# Blutooth.net
KiCad netlist of a schematic drawn in Altium Designer
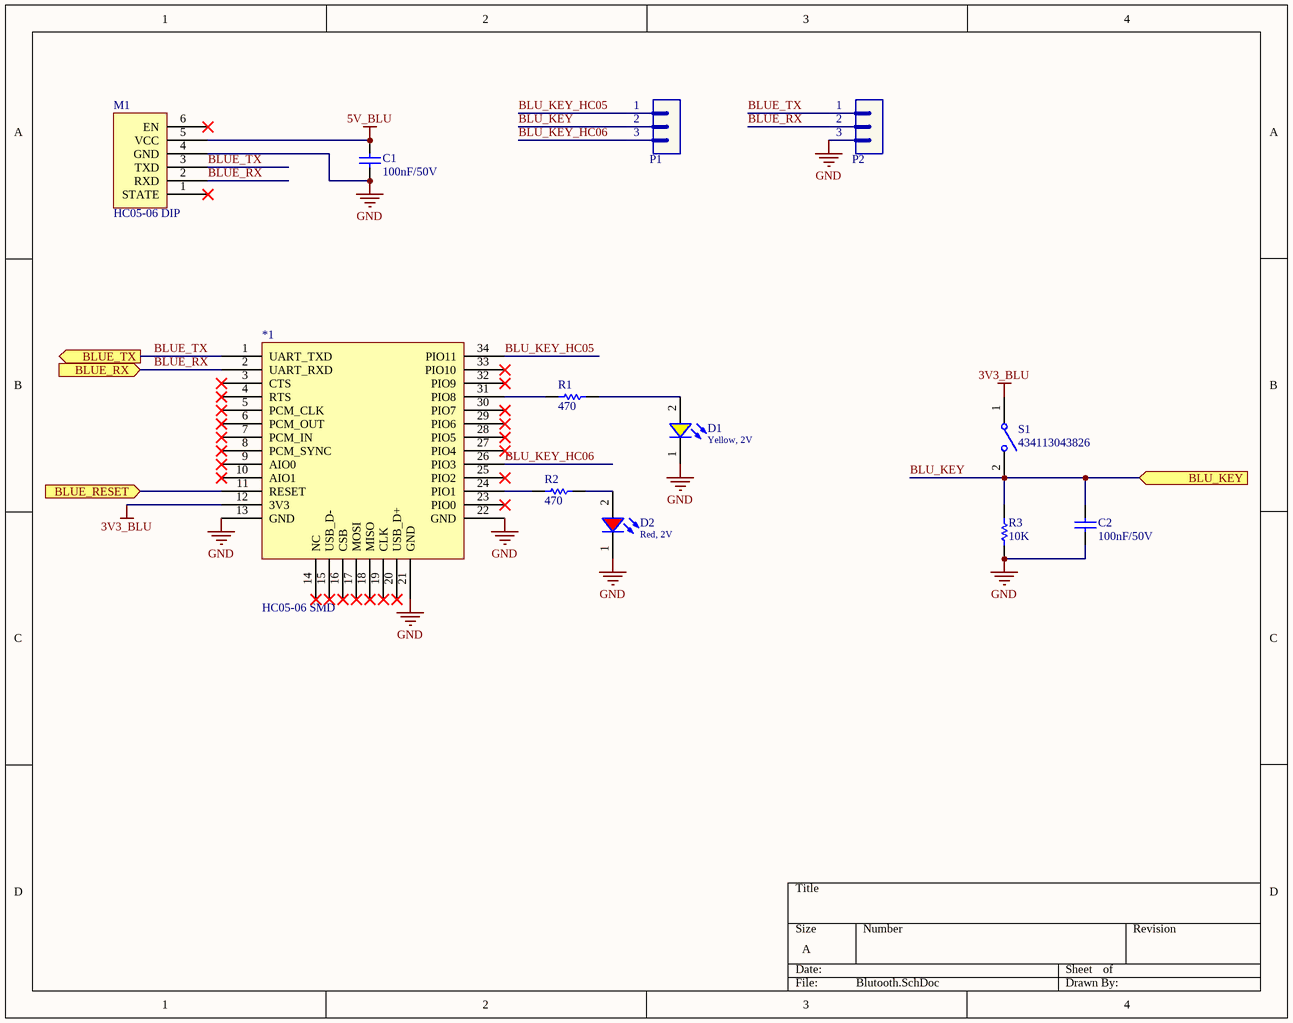
[diagram p0: Blutooth.SchDoc]

(export (version "E")
  (design (tool "Eeschema 10.0.6"))
  (components
    (comp (ref "*1")
      (value "HC05-06 SMD")
      (footprint "HC05-06 SMD")
      (libsource (lib "chicken") (part "HC05-06 SMD"))
    )
    (comp (ref "C1")
      (value "100nF/50V")
      (footprint "CAP-SM-0805")
      (description "CAP CER 0.1UF 50V Y5V 0805")
      (fields
        (field (name "MANUFACTURER") "Samsung Electro-Mechanics")
        (field (name "MANUFACTURER PART NUMBER") "CL21F104ZBCNNNC")
      )
      (libsource (lib "Capacitor") (part "Cap-100nF-50V-0805"))
    )
    (comp (ref "C2")
      (value "100nF/50V")
      (footprint "CAP-SM-0805")
      (description "CAP CER 0.1UF 50V Y5V 0805")
      (fields
        (field (name "MANUFACTURER") "Samsung Electro-Mechanics")
        (field (name "MANUFACTURER PART NUMBER") "CL21F104ZBCNNNC")
      )
      (libsource (lib "Capacitor") (part "Cap-100nF-50V-0805"))
    )
    (comp (ref "D1")
      (value "Yellow, 2V")
      (footprint "WL-SMCW_0805")
      (description "WL-SMCW SMT Mono-color Chip LED Waterclear, size 0805, Yellow, 2V, 140deg")
      (fields (field (name "PART NUMBER") "150080YS75000") (field (name "PUBLISHER") "Wurth Elektronik"))
      (libsource (lib "150080BS75000_Altium_WL-SMCW_rev20a") (part "150080YS75000"))
    )
    (comp (ref "D2")
      (value "Red, 2V")
      (footprint "WL-SMCW_0805")
      (description "WL-SMCW SMT Mono-color Chip LED Waterclear, size 0805, Red, 2V, 140deg")
      (fields (field (name "PART NUMBER") "150080RS75000") (field (name "PUBLISHER") "Wurth Elektronik"))
      (libsource (lib "150080BS75000_Altium_WL-SMCW_rev20a") (part "150080RS75000"))
    )
    (comp (ref "M1")
      (value "HC05-06 DIP")
      (footprint "HC05-06 DIP")
      (libsource (lib "chicken") (part "HC05-06 DIP"))
    )
    (comp (ref "P1")
      (value "Header 3")
      (footprint "JP3")
      (description "Header, 3-Pin")
      (fields (field (name "PUBLISHER") "Altium Limited"))
      (libsource (lib "Header-connector") (part "Header 3"))
    )
    (comp (ref "P2")
      (value "Header 3")
      (footprint "JP3")
      (description "Header, 3-Pin")
      (fields (field (name "PUBLISHER") "Altium Limited"))
      (libsource (lib "Header-connector") (part "Header 3"))
    )
    (comp (ref "R1")
      (value "470")
      (footprint "Resistor:RES-SM-0805")
      (description "RES 470 OHM JUMPER 0805")
      (fields
        (field (name "MANUFACTURER") "YAG6006CT-ND")
        (field (name "MANUFACTURER PART NUMBER") "PE0805FRF7W0R047L")
      )
      (libsource (lib "Resistor") (part "Res-470-0805"))
    )
    (comp (ref "R2")
      (value "470")
      (footprint "Resistor:RES-SM-0805")
      (description "RES 470 OHM JUMPER 0805")
      (fields
        (field (name "MANUFACTURER") "YAG6006CT-ND")
        (field (name "MANUFACTURER PART NUMBER") "PE0805FRF7W0R047L")
      )
      (libsource (lib "Resistor") (part "Res-470-0805"))
    )
    (comp (ref "R3")
      (value "10K")
      (footprint "Resistor:RES-SM-0805")
      (description "RES 10K OHM 1% 1/4W 0805")
      (fields
        (field (name "MANUFACTURER") "Stackpole Electronics Inc")
        (field (name "MANUFACTURER PART NUMBER") "RNCP0805FTD10K0")
      )
      (libsource (lib "Resistor") (part "Res-10k-0805"))
    )
    (comp (ref "S1")
      (value "434113043826")
      (footprint "434113043826")
      (description "WS-TASV J-Bend SMT Tact Switch 6x3.5mm, height 4.3mm, 260gf")
      (fields (field (name "PUBLISHER") "Wurth Elektronik"))
      (libsource (lib "434113043826_Altium_WS-TASV_rev20a") (part "434113043826"))
    )
  )
  (nets
    (net (code "1") (name "/BLUE_RESET") (class "Default")
      (node (ref "*1") (pin "11") (pinfunction "RESET_11") (pintype "passive"))
    )
    (net (code "2") (name "/BLUE_RX") (class "Default")
      (node (ref "*1") (pin "2") (pinfunction "UART_RXD_2") (pintype "passive"))
      (node (ref "M1") (pin "2") (pinfunction "RXD_2") (pintype "passive"))
      (node (ref "P2") (pin "2") (pinfunction "2_2") (pintype "passive"))
    )
    (net (code "3") (name "/BLUE_TX") (class "Default")
      (node (ref "*1") (pin "1") (pinfunction "UART_TXD_1") (pintype "passive"))
      (node (ref "M1") (pin "3") (pinfunction "TXD_3") (pintype "passive"))
      (node (ref "P2") (pin "1") (pinfunction "1_1") (pintype "passive"))
    )
    (net (code "4") (name "/BLU_KEY") (class "Default")
      (node (ref "C2") (pin "2") (pinfunction "2_2") (pintype "passive"))
      (node (ref "P1") (pin "2") (pinfunction "2_2") (pintype "passive"))
      (node (ref "R3") (pin "1") (pinfunction "1_1") (pintype "passive"))
      (node (ref "S1") (pin "2") (pinfunction "2_2") (pintype "passive"))
    )
    (net (code "5") (name "/BLU_KEY_HC05") (class "Default")
      (node (ref "*1") (pin "34") (pinfunction "PIO11_34") (pintype "passive"))
      (node (ref "P1") (pin "1") (pinfunction "1_1") (pintype "passive"))
    )
    (net (code "6") (name "/BLU_KEY_HC06") (class "Default")
      (node (ref "*1") (pin "26") (pinfunction "PIO3_26") (pintype "passive"))
      (node (ref "P1") (pin "3") (pinfunction "3_3") (pintype "passive"))
    )
    (net (code "7") (name "3V3_BLU") (class "Default")
      (node (ref "*1") (pin "12") (pinfunction "3V3_12") (pintype "passive"))
      (node (ref "S1") (pin "1") (pinfunction "1_1") (pintype "passive"))
    )
    (net (code "8") (name "5V_BLU") (class "Default")
      (node (ref "C1") (pin "2") (pinfunction "2_2") (pintype "passive"))
      (node (ref "M1") (pin "5") (pinfunction "VCC_5") (pintype "passive"))
    )
    (net (code "9") (name "GND") (class "Default")
      (node (ref "*1") (pin "13") (pinfunction "GND_13") (pintype "passive"))
      (node (ref "*1") (pin "21") (pinfunction "GND_21") (pintype "passive"))
      (node (ref "*1") (pin "22") (pinfunction "GND_22") (pintype "passive"))
      (node (ref "C1") (pin "1") (pinfunction "1_1") (pintype "passive"))
      (node (ref "C2") (pin "1") (pinfunction "1_1") (pintype "passive"))
      (node (ref "D1") (pin "1") (pinfunction "K_1") (pintype "passive"))
      (node (ref "D2") (pin "1") (pinfunction "K_1") (pintype "passive"))
      (node (ref "M1") (pin "4") (pinfunction "GND_4") (pintype "passive"))
      (node (ref "P2") (pin "3") (pinfunction "3_3") (pintype "passive"))
      (node (ref "R3") (pin "2") (pinfunction "2_2") (pintype "passive"))
    )
    (net (code "10") (name "Net-(*1-PIO1)") (class "Default")
      (node (ref "*1") (pin "24") (pinfunction "PIO1_24") (pintype "passive"))
      (node (ref "R2") (pin "1") (pinfunction "1_1") (pintype "passive"))
    )
    (net (code "11") (name "Net-(*1-PIO8)") (class "Default")
      (node (ref "*1") (pin "31") (pinfunction "PIO8_31") (pintype "passive"))
      (node (ref "R1") (pin "1") (pinfunction "1_1") (pintype "passive"))
    )
    (net (code "12") (name "Net-(D1-A)") (class "Default")
      (node (ref "D1") (pin "2") (pinfunction "A_2") (pintype "passive"))
      (node (ref "R1") (pin "2") (pinfunction "2_2") (pintype "passive"))
    )
    (net (code "13") (name "Net-(D2-A)") (class "Default")
      (node (ref "D2") (pin "2") (pinfunction "A_2") (pintype "passive"))
      (node (ref "R2") (pin "2") (pinfunction "2_2") (pintype "passive"))
    )
    (net (code "14") (name "unconnected-(*1-AIO0-Pad9)") (class "Default")
      (node (ref "*1") (pin "9") (pinfunction "AIO0_9") (pintype "passive+no_connect"))
    )
    (net (code "15") (name "unconnected-(*1-AIO1-Pad10)") (class "Default")
      (node (ref "*1") (pin "10") (pinfunction "AIO1_10") (pintype "passive+no_connect"))
    )
    (net (code "16") (name "unconnected-(*1-CLK-Pad19)") (class "Default")
      (node (ref "*1") (pin "19") (pinfunction "CLK_19") (pintype "passive+no_connect"))
    )
    (net (code "17") (name "unconnected-(*1-CSB-Pad16)") (class "Default")
      (node (ref "*1") (pin "16") (pinfunction "CSB_16") (pintype "passive+no_connect"))
    )
    (net (code "18") (name "unconnected-(*1-CTS-Pad3)") (class "Default")
      (node (ref "*1") (pin "3") (pinfunction "CTS_3") (pintype "passive+no_connect"))
    )
    (net (code "19") (name "unconnected-(*1-MISO-Pad18)") (class "Default")
      (node (ref "*1") (pin "18") (pinfunction "MISO_18") (pintype "passive+no_connect"))
    )
    (net (code "20") (name "unconnected-(*1-MOSI-Pad17)") (class "Default")
      (node (ref "*1") (pin "17") (pinfunction "MOSI_17") (pintype "passive+no_connect"))
    )
    (net (code "21") (name "unconnected-(*1-NC-Pad14)") (class "Default")
      (node (ref "*1") (pin "14") (pinfunction "NC_14") (pintype "passive+no_connect"))
    )
    (net (code "22") (name "unconnected-(*1-PCM_CLK-Pad5)") (class "Default")
      (node (ref "*1") (pin "5") (pinfunction "PCM_CLK_5") (pintype "passive+no_connect"))
    )
    (net (code "23") (name "unconnected-(*1-PCM_IN-Pad7)") (class "Default")
      (node (ref "*1") (pin "7") (pinfunction "PCM_IN_7") (pintype "passive+no_connect"))
    )
    (net (code "24") (name "unconnected-(*1-PCM_OUT-Pad6)") (class "Default")
      (node (ref "*1") (pin "6") (pinfunction "PCM_OUT_6") (pintype "passive+no_connect"))
    )
    (net (code "25") (name "unconnected-(*1-PCM_SYNC-Pad8)") (class "Default")
      (node (ref "*1") (pin "8") (pinfunction "PCM_SYNC_8") (pintype "passive+no_connect"))
    )
    (net (code "26") (name "unconnected-(*1-PIO0-Pad23)") (class "Default")
      (node (ref "*1") (pin "23") (pinfunction "PIO0_23") (pintype "passive+no_connect"))
    )
    (net (code "27") (name "unconnected-(*1-PIO2-Pad25)") (class "Default")
      (node (ref "*1") (pin "25") (pinfunction "PIO2_25") (pintype "passive+no_connect"))
    )
    (net (code "28") (name "unconnected-(*1-PIO4-Pad27)") (class "Default")
      (node (ref "*1") (pin "27") (pinfunction "PIO4_27") (pintype "passive+no_connect"))
    )
    (net (code "29") (name "unconnected-(*1-PIO5-Pad28)") (class "Default")
      (node (ref "*1") (pin "28") (pinfunction "PIO5_28") (pintype "passive+no_connect"))
    )
    (net (code "30") (name "unconnected-(*1-PIO6-Pad29)") (class "Default")
      (node (ref "*1") (pin "29") (pinfunction "PIO6_29") (pintype "passive+no_connect"))
    )
    (net (code "31") (name "unconnected-(*1-PIO7-Pad30)") (class "Default")
      (node (ref "*1") (pin "30") (pinfunction "PIO7_30") (pintype "passive+no_connect"))
    )
    (net (code "32") (name "unconnected-(*1-PIO9-Pad32)") (class "Default")
      (node (ref "*1") (pin "32") (pinfunction "PIO9_32") (pintype "passive+no_connect"))
    )
    (net (code "33") (name "unconnected-(*1-PIO10-Pad33)") (class "Default")
      (node (ref "*1") (pin "33") (pinfunction "PIO10_33") (pintype "passive+no_connect"))
    )
    (net (code "34") (name "unconnected-(*1-RTS-Pad4)") (class "Default")
      (node (ref "*1") (pin "4") (pinfunction "RTS_4") (pintype "passive+no_connect"))
    )
    (net (code "35") (name "unconnected-(*1-USB_D+-Pad20)") (class "Default")
      (node (ref "*1") (pin "20") (pinfunction "USB_D+_20") (pintype "passive+no_connect"))
    )
    (net (code "36") (name "unconnected-(*1-USB_D--Pad15)") (class "Default")
      (node (ref "*1") (pin "15") (pinfunction "USB_D-_15") (pintype "passive+no_connect"))
    )
    (net (code "37") (name "unconnected-(M1-EN-Pad6)") (class "Default")
      (node (ref "M1") (pin "6") (pinfunction "EN_6") (pintype "passive+no_connect"))
    )
    (net (code "38") (name "unconnected-(M1-STATE-Pad1)") (class "Default")
      (node (ref "M1") (pin "1") (pinfunction "STATE_1") (pintype "passive+no_connect"))
    )
  )
)
